# Brakelight_v3.net
KiCad netlist of a schematic drawn in EAGLE
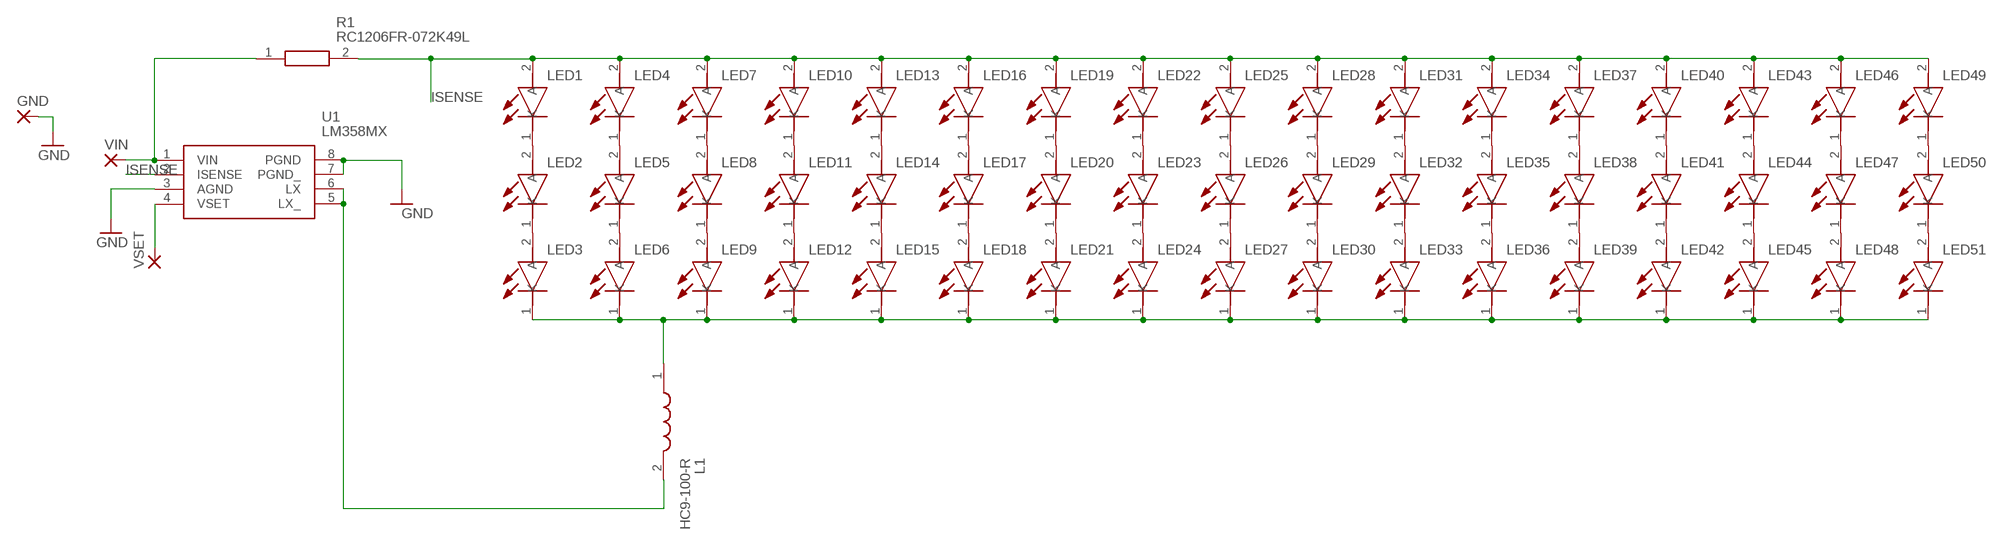
[diagram p0: schematic, sheet 1]

(export (version "E")
  (design (tool "Eeschema 10.0.6"))
  (components
    (comp (ref "GND")
      (value "2,54/1,1")
      (footprint "eagle-import:2,54_1,1")
      (libsource (lib "eagle-import") (part "2,54/1,1"))
    )
    (comp (ref "L1")
      (value "HC9-100-R")
      (footprint "eagle-import:INDPM141131X770N")
      (fields (field (name "MOUSER_PART_NUMBER") "704-HC9-100-R"))
      (libsource (lib "eagle-import") (part "HC9-100-R"))
    )
    (comp (ref "LED1")
      (value "SSL-LX5093TC")
      (footprint "eagle-import:SSL-LX5093SGC_B")
      (fields (field (name "MOUSER_PART_NUMBER") "696-SSL-LX5093TC"))
      (libsource (lib "eagle-import") (part "SSL-LX5093TC"))
    )
    (comp (ref "LED2")
      (value "SSL-LX5093TC")
      (footprint "eagle-import:SSL-LX5093SGC_B")
      (fields (field (name "MOUSER_PART_NUMBER") "696-SSL-LX5093TC"))
      (libsource (lib "eagle-import") (part "SSL-LX5093TC"))
    )
    (comp (ref "LED3")
      (value "SSL-LX5093TC")
      (footprint "eagle-import:SSL-LX5093SGC_B")
      (fields (field (name "MOUSER_PART_NUMBER") "696-SSL-LX5093TC"))
      (libsource (lib "eagle-import") (part "SSL-LX5093TC"))
    )
    (comp (ref "LED4")
      (value "SSL-LX5093TC")
      (footprint "eagle-import:SSL-LX5093SGC_B")
      (fields (field (name "MOUSER_PART_NUMBER") "696-SSL-LX5093TC"))
      (libsource (lib "eagle-import") (part "SSL-LX5093TC"))
    )
    (comp (ref "LED5")
      (value "SSL-LX5093TC")
      (footprint "eagle-import:SSL-LX5093SGC_B")
      (fields (field (name "MOUSER_PART_NUMBER") "696-SSL-LX5093TC"))
      (libsource (lib "eagle-import") (part "SSL-LX5093TC"))
    )
    (comp (ref "LED6")
      (value "SSL-LX5093TC")
      (footprint "eagle-import:SSL-LX5093SGC_B")
      (fields (field (name "MOUSER_PART_NUMBER") "696-SSL-LX5093TC"))
      (libsource (lib "eagle-import") (part "SSL-LX5093TC"))
    )
    (comp (ref "LED7")
      (value "SSL-LX5093TC")
      (footprint "eagle-import:SSL-LX5093SGC_B")
      (fields (field (name "MOUSER_PART_NUMBER") "696-SSL-LX5093TC"))
      (libsource (lib "eagle-import") (part "SSL-LX5093TC"))
    )
    (comp (ref "LED8")
      (value "SSL-LX5093TC")
      (footprint "eagle-import:SSL-LX5093SGC_B")
      (fields (field (name "MOUSER_PART_NUMBER") "696-SSL-LX5093TC"))
      (libsource (lib "eagle-import") (part "SSL-LX5093TC"))
    )
    (comp (ref "LED9")
      (value "SSL-LX5093TC")
      (footprint "eagle-import:SSL-LX5093SGC_B")
      (fields (field (name "MOUSER_PART_NUMBER") "696-SSL-LX5093TC"))
      (libsource (lib "eagle-import") (part "SSL-LX5093TC"))
    )
    (comp (ref "LED10")
      (value "SSL-LX5093TC")
      (footprint "eagle-import:SSL-LX5093SGC_B")
      (fields (field (name "MOUSER_PART_NUMBER") "696-SSL-LX5093TC"))
      (libsource (lib "eagle-import") (part "SSL-LX5093TC"))
    )
    (comp (ref "LED11")
      (value "SSL-LX5093TC")
      (footprint "eagle-import:SSL-LX5093SGC_B")
      (fields (field (name "MOUSER_PART_NUMBER") "696-SSL-LX5093TC"))
      (libsource (lib "eagle-import") (part "SSL-LX5093TC"))
    )
    (comp (ref "LED12")
      (value "SSL-LX5093TC")
      (footprint "eagle-import:SSL-LX5093SGC_B")
      (fields (field (name "MOUSER_PART_NUMBER") "696-SSL-LX5093TC"))
      (libsource (lib "eagle-import") (part "SSL-LX5093TC"))
    )
    (comp (ref "LED13")
      (value "SSL-LX5093TC")
      (footprint "eagle-import:SSL-LX5093SGC_B")
      (fields (field (name "MOUSER_PART_NUMBER") "696-SSL-LX5093TC"))
      (libsource (lib "eagle-import") (part "SSL-LX5093TC"))
    )
    (comp (ref "LED14")
      (value "SSL-LX5093TC")
      (footprint "eagle-import:SSL-LX5093SGC_B")
      (fields (field (name "MOUSER_PART_NUMBER") "696-SSL-LX5093TC"))
      (libsource (lib "eagle-import") (part "SSL-LX5093TC"))
    )
    (comp (ref "LED15")
      (value "SSL-LX5093TC")
      (footprint "eagle-import:SSL-LX5093SGC_B")
      (fields (field (name "MOUSER_PART_NUMBER") "696-SSL-LX5093TC"))
      (libsource (lib "eagle-import") (part "SSL-LX5093TC"))
    )
    (comp (ref "LED16")
      (value "SSL-LX5093TC")
      (footprint "eagle-import:SSL-LX5093SGC_B")
      (fields (field (name "MOUSER_PART_NUMBER") "696-SSL-LX5093TC"))
      (libsource (lib "eagle-import") (part "SSL-LX5093TC"))
    )
    (comp (ref "LED17")
      (value "SSL-LX5093TC")
      (footprint "eagle-import:SSL-LX5093SGC_B")
      (fields (field (name "MOUSER_PART_NUMBER") "696-SSL-LX5093TC"))
      (libsource (lib "eagle-import") (part "SSL-LX5093TC"))
    )
    (comp (ref "LED18")
      (value "SSL-LX5093TC")
      (footprint "eagle-import:SSL-LX5093SGC_B")
      (fields (field (name "MOUSER_PART_NUMBER") "696-SSL-LX5093TC"))
      (libsource (lib "eagle-import") (part "SSL-LX5093TC"))
    )
    (comp (ref "LED19")
      (value "SSL-LX5093TC")
      (footprint "eagle-import:SSL-LX5093SGC_B")
      (fields (field (name "MOUSER_PART_NUMBER") "696-SSL-LX5093TC"))
      (libsource (lib "eagle-import") (part "SSL-LX5093TC"))
    )
    (comp (ref "LED20")
      (value "SSL-LX5093TC")
      (footprint "eagle-import:SSL-LX5093SGC_B")
      (fields (field (name "MOUSER_PART_NUMBER") "696-SSL-LX5093TC"))
      (libsource (lib "eagle-import") (part "SSL-LX5093TC"))
    )
    (comp (ref "LED21")
      (value "SSL-LX5093TC")
      (footprint "eagle-import:SSL-LX5093SGC_B")
      (fields (field (name "MOUSER_PART_NUMBER") "696-SSL-LX5093TC"))
      (libsource (lib "eagle-import") (part "SSL-LX5093TC"))
    )
    (comp (ref "LED22")
      (value "SSL-LX5093TC")
      (footprint "eagle-import:SSL-LX5093SGC_B")
      (fields (field (name "MOUSER_PART_NUMBER") "696-SSL-LX5093TC"))
      (libsource (lib "eagle-import") (part "SSL-LX5093TC"))
    )
    (comp (ref "LED23")
      (value "SSL-LX5093TC")
      (footprint "eagle-import:SSL-LX5093SGC_B")
      (fields (field (name "MOUSER_PART_NUMBER") "696-SSL-LX5093TC"))
      (libsource (lib "eagle-import") (part "SSL-LX5093TC"))
    )
    (comp (ref "LED24")
      (value "SSL-LX5093TC")
      (footprint "eagle-import:SSL-LX5093SGC_B")
      (fields (field (name "MOUSER_PART_NUMBER") "696-SSL-LX5093TC"))
      (libsource (lib "eagle-import") (part "SSL-LX5093TC"))
    )
    (comp (ref "LED25")
      (value "SSL-LX5093TC")
      (footprint "eagle-import:SSL-LX5093SGC_B")
      (fields (field (name "MOUSER_PART_NUMBER") "696-SSL-LX5093TC"))
      (libsource (lib "eagle-import") (part "SSL-LX5093TC"))
    )
    (comp (ref "LED26")
      (value "SSL-LX5093TC")
      (footprint "eagle-import:SSL-LX5093SGC_B")
      (fields (field (name "MOUSER_PART_NUMBER") "696-SSL-LX5093TC"))
      (libsource (lib "eagle-import") (part "SSL-LX5093TC"))
    )
    (comp (ref "LED27")
      (value "SSL-LX5093TC")
      (footprint "eagle-import:SSL-LX5093SGC_B")
      (fields (field (name "MOUSER_PART_NUMBER") "696-SSL-LX5093TC"))
      (libsource (lib "eagle-import") (part "SSL-LX5093TC"))
    )
    (comp (ref "LED28")
      (value "SSL-LX5093TC")
      (footprint "eagle-import:SSL-LX5093SGC_B")
      (fields (field (name "MOUSER_PART_NUMBER") "696-SSL-LX5093TC"))
      (libsource (lib "eagle-import") (part "SSL-LX5093TC"))
    )
    (comp (ref "LED29")
      (value "SSL-LX5093TC")
      (footprint "eagle-import:SSL-LX5093SGC_B")
      (fields (field (name "MOUSER_PART_NUMBER") "696-SSL-LX5093TC"))
      (libsource (lib "eagle-import") (part "SSL-LX5093TC"))
    )
    (comp (ref "LED30")
      (value "SSL-LX5093TC")
      (footprint "eagle-import:SSL-LX5093SGC_B")
      (fields (field (name "MOUSER_PART_NUMBER") "696-SSL-LX5093TC"))
      (libsource (lib "eagle-import") (part "SSL-LX5093TC"))
    )
    (comp (ref "LED31")
      (value "SSL-LX5093TC")
      (footprint "eagle-import:SSL-LX5093SGC_B")
      (fields (field (name "MOUSER_PART_NUMBER") "696-SSL-LX5093TC"))
      (libsource (lib "eagle-import") (part "SSL-LX5093TC"))
    )
    (comp (ref "LED32")
      (value "SSL-LX5093TC")
      (footprint "eagle-import:SSL-LX5093SGC_B")
      (fields (field (name "MOUSER_PART_NUMBER") "696-SSL-LX5093TC"))
      (libsource (lib "eagle-import") (part "SSL-LX5093TC"))
    )
    (comp (ref "LED33")
      (value "SSL-LX5093TC")
      (footprint "eagle-import:SSL-LX5093SGC_B")
      (fields (field (name "MOUSER_PART_NUMBER") "696-SSL-LX5093TC"))
      (libsource (lib "eagle-import") (part "SSL-LX5093TC"))
    )
    (comp (ref "LED34")
      (value "SSL-LX5093TC")
      (footprint "eagle-import:SSL-LX5093SGC_B")
      (fields (field (name "MOUSER_PART_NUMBER") "696-SSL-LX5093TC"))
      (libsource (lib "eagle-import") (part "SSL-LX5093TC"))
    )
    (comp (ref "LED35")
      (value "SSL-LX5093TC")
      (footprint "eagle-import:SSL-LX5093SGC_B")
      (fields (field (name "MOUSER_PART_NUMBER") "696-SSL-LX5093TC"))
      (libsource (lib "eagle-import") (part "SSL-LX5093TC"))
    )
    (comp (ref "LED36")
      (value "SSL-LX5093TC")
      (footprint "eagle-import:SSL-LX5093SGC_B")
      (fields (field (name "MOUSER_PART_NUMBER") "696-SSL-LX5093TC"))
      (libsource (lib "eagle-import") (part "SSL-LX5093TC"))
    )
    (comp (ref "LED37")
      (value "SSL-LX5093TC")
      (footprint "eagle-import:SSL-LX5093SGC_B")
      (fields (field (name "MOUSER_PART_NUMBER") "696-SSL-LX5093TC"))
      (libsource (lib "eagle-import") (part "SSL-LX5093TC"))
    )
    (comp (ref "LED38")
      (value "SSL-LX5093TC")
      (footprint "eagle-import:SSL-LX5093SGC_B")
      (fields (field (name "MOUSER_PART_NUMBER") "696-SSL-LX5093TC"))
      (libsource (lib "eagle-import") (part "SSL-LX5093TC"))
    )
    (comp (ref "LED39")
      (value "SSL-LX5093TC")
      (footprint "eagle-import:SSL-LX5093SGC_B")
      (fields (field (name "MOUSER_PART_NUMBER") "696-SSL-LX5093TC"))
      (libsource (lib "eagle-import") (part "SSL-LX5093TC"))
    )
    (comp (ref "LED40")
      (value "SSL-LX5093TC")
      (footprint "eagle-import:SSL-LX5093SGC_B")
      (fields (field (name "MOUSER_PART_NUMBER") "696-SSL-LX5093TC"))
      (libsource (lib "eagle-import") (part "SSL-LX5093TC"))
    )
    (comp (ref "LED41")
      (value "SSL-LX5093TC")
      (footprint "eagle-import:SSL-LX5093SGC_B")
      (fields (field (name "MOUSER_PART_NUMBER") "696-SSL-LX5093TC"))
      (libsource (lib "eagle-import") (part "SSL-LX5093TC"))
    )
    (comp (ref "LED42")
      (value "SSL-LX5093TC")
      (footprint "eagle-import:SSL-LX5093SGC_B")
      (fields (field (name "MOUSER_PART_NUMBER") "696-SSL-LX5093TC"))
      (libsource (lib "eagle-import") (part "SSL-LX5093TC"))
    )
    (comp (ref "LED43")
      (value "SSL-LX5093TC")
      (footprint "eagle-import:SSL-LX5093SGC_B")
      (fields (field (name "MOUSER_PART_NUMBER") "696-SSL-LX5093TC"))
      (libsource (lib "eagle-import") (part "SSL-LX5093TC"))
    )
    (comp (ref "LED44")
      (value "SSL-LX5093TC")
      (footprint "eagle-import:SSL-LX5093SGC_B")
      (fields (field (name "MOUSER_PART_NUMBER") "696-SSL-LX5093TC"))
      (libsource (lib "eagle-import") (part "SSL-LX5093TC"))
    )
    (comp (ref "LED45")
      (value "SSL-LX5093TC")
      (footprint "eagle-import:SSL-LX5093SGC_B")
      (fields (field (name "MOUSER_PART_NUMBER") "696-SSL-LX5093TC"))
      (libsource (lib "eagle-import") (part "SSL-LX5093TC"))
    )
    (comp (ref "LED46")
      (value "SSL-LX5093TC")
      (footprint "eagle-import:SSL-LX5093SGC_B")
      (fields (field (name "MOUSER_PART_NUMBER") "696-SSL-LX5093TC"))
      (libsource (lib "eagle-import") (part "SSL-LX5093TC"))
    )
    (comp (ref "LED47")
      (value "SSL-LX5093TC")
      (footprint "eagle-import:SSL-LX5093SGC_B")
      (fields (field (name "MOUSER_PART_NUMBER") "696-SSL-LX5093TC"))
      (libsource (lib "eagle-import") (part "SSL-LX5093TC"))
    )
    (comp (ref "LED48")
      (value "SSL-LX5093TC")
      (footprint "eagle-import:SSL-LX5093SGC_B")
      (fields (field (name "MOUSER_PART_NUMBER") "696-SSL-LX5093TC"))
      (libsource (lib "eagle-import") (part "SSL-LX5093TC"))
    )
    (comp (ref "LED49")
      (value "SSL-LX5093TC")
      (footprint "eagle-import:SSL-LX5093SGC_B")
      (fields (field (name "MOUSER_PART_NUMBER") "696-SSL-LX5093TC"))
      (libsource (lib "eagle-import") (part "SSL-LX5093TC"))
    )
    (comp (ref "LED50")
      (value "SSL-LX5093TC")
      (footprint "eagle-import:SSL-LX5093SGC_B")
      (fields (field (name "MOUSER_PART_NUMBER") "696-SSL-LX5093TC"))
      (libsource (lib "eagle-import") (part "SSL-LX5093TC"))
    )
    (comp (ref "LED51")
      (value "SSL-LX5093TC")
      (footprint "eagle-import:SSL-LX5093SGC_B")
      (fields (field (name "MOUSER_PART_NUMBER") "696-SSL-LX5093TC"))
      (libsource (lib "eagle-import") (part "SSL-LX5093TC"))
    )
    (comp (ref "R1")
      (value "RC1206FR-072K49L")
      (footprint "eagle-import:RESC3116X65N")
      (fields (field (name "MOUSER_PART_NUMBER") "603-RC1206FR-072K49L"))
      (libsource (lib "eagle-import") (part "RC1206FR-072K49L"))
    )
    (comp (ref "U1")
      (value "LM358MX")
      (footprint "eagle-import:SOP127P600X180-8N")
      (fields (field (name "MOUSER_PART_NUMBER") "512-LM358MX"))
      (libsource (lib "eagle-import") (part "LM358MX"))
    )
    (comp (ref "VIN")
      (value "2,54/1,1")
      (footprint "eagle-import:2,54_1,1")
      (libsource (lib "eagle-import") (part "2,54/1,1"))
    )
    (comp (ref "VSET")
      (value "2,54/1,1")
      (footprint "eagle-import:2,54_1,1")
      (libsource (lib "eagle-import") (part "2,54/1,1"))
    )
  )
  (nets
    (net (code "1") (name "/ISENSE") (class "Default")
      (node (ref "LED1") (pin "2") (pinfunction "A_2") (pintype "bidirectional"))
      (node (ref "LED10") (pin "2") (pinfunction "A_2") (pintype "bidirectional"))
      (node (ref "LED13") (pin "2") (pinfunction "A_2") (pintype "bidirectional"))
      (node (ref "LED16") (pin "2") (pinfunction "A_2") (pintype "bidirectional"))
      (node (ref "LED19") (pin "2") (pinfunction "A_2") (pintype "bidirectional"))
      (node (ref "LED22") (pin "2") (pinfunction "A_2") (pintype "bidirectional"))
      (node (ref "LED25") (pin "2") (pinfunction "A_2") (pintype "bidirectional"))
      (node (ref "LED28") (pin "2") (pinfunction "A_2") (pintype "bidirectional"))
      (node (ref "LED31") (pin "2") (pinfunction "A_2") (pintype "bidirectional"))
      (node (ref "LED34") (pin "2") (pinfunction "A_2") (pintype "bidirectional"))
      (node (ref "LED37") (pin "2") (pinfunction "A_2") (pintype "bidirectional"))
      (node (ref "LED4") (pin "2") (pinfunction "A_2") (pintype "bidirectional"))
      (node (ref "LED40") (pin "2") (pinfunction "A_2") (pintype "bidirectional"))
      (node (ref "LED43") (pin "2") (pinfunction "A_2") (pintype "bidirectional"))
      (node (ref "LED46") (pin "2") (pinfunction "A_2") (pintype "bidirectional"))
      (node (ref "LED49") (pin "2") (pinfunction "A_2") (pintype "bidirectional"))
      (node (ref "LED7") (pin "2") (pinfunction "A_2") (pintype "bidirectional"))
      (node (ref "R1") (pin "2") (pinfunction "2_2") (pintype "bidirectional"))
      (node (ref "U1") (pin "2") (pinfunction "ISENSE_2") (pintype "bidirectional"))
    )
    (net (code "2") (name "GND") (class "Default")
      (node (ref "GND") (pin "1") (pinfunction "P_1") (pintype "passive"))
      (node (ref "U1") (pin "3") (pinfunction "AGND_3") (pintype "bidirectional"))
      (node (ref "U1") (pin "7") (pinfunction "PGND__7") (pintype "bidirectional"))
      (node (ref "U1") (pin "8") (pinfunction "PGND_8") (pintype "bidirectional"))
    )
    (net (code "3") (name "Net-(LED1-K)") (class "Default")
      (node (ref "LED1") (pin "1") (pinfunction "K_1") (pintype "bidirectional"))
      (node (ref "LED2") (pin "2") (pinfunction "A_2") (pintype "bidirectional"))
    )
    (net (code "4") (name "Net-(LED2-K)") (class "Default")
      (node (ref "LED2") (pin "1") (pinfunction "K_1") (pintype "bidirectional"))
      (node (ref "LED3") (pin "2") (pinfunction "A_2") (pintype "bidirectional"))
    )
    (net (code "5") (name "Net-(LED4-K)") (class "Default")
      (node (ref "LED4") (pin "1") (pinfunction "K_1") (pintype "bidirectional"))
      (node (ref "LED5") (pin "2") (pinfunction "A_2") (pintype "bidirectional"))
    )
    (net (code "6") (name "Net-(LED5-K)") (class "Default")
      (node (ref "LED5") (pin "1") (pinfunction "K_1") (pintype "bidirectional"))
      (node (ref "LED6") (pin "2") (pinfunction "A_2") (pintype "bidirectional"))
    )
    (net (code "7") (name "Net-(LED7-K)") (class "Default")
      (node (ref "LED7") (pin "1") (pinfunction "K_1") (pintype "bidirectional"))
      (node (ref "LED8") (pin "2") (pinfunction "A_2") (pintype "bidirectional"))
    )
    (net (code "8") (name "Net-(LED8-K)") (class "Default")
      (node (ref "LED8") (pin "1") (pinfunction "K_1") (pintype "bidirectional"))
      (node (ref "LED9") (pin "2") (pinfunction "A_2") (pintype "bidirectional"))
    )
    (net (code "9") (name "Net-(LED10-K)") (class "Default")
      (node (ref "LED10") (pin "1") (pinfunction "K_1") (pintype "bidirectional"))
      (node (ref "LED11") (pin "2") (pinfunction "A_2") (pintype "bidirectional"))
    )
    (net (code "10") (name "Net-(LED11-K)") (class "Default")
      (node (ref "LED11") (pin "1") (pinfunction "K_1") (pintype "bidirectional"))
      (node (ref "LED12") (pin "2") (pinfunction "A_2") (pintype "bidirectional"))
    )
    (net (code "11") (name "Net-(LED12-K)") (class "Default")
      (node (ref "L1") (pin "1") (pinfunction "1_1") (pintype "bidirectional"))
      (node (ref "LED12") (pin "1") (pinfunction "K_1") (pintype "bidirectional"))
      (node (ref "LED15") (pin "1") (pinfunction "K_1") (pintype "bidirectional"))
      (node (ref "LED18") (pin "1") (pinfunction "K_1") (pintype "bidirectional"))
      (node (ref "LED21") (pin "1") (pinfunction "K_1") (pintype "bidirectional"))
      (node (ref "LED24") (pin "1") (pinfunction "K_1") (pintype "bidirectional"))
      (node (ref "LED27") (pin "1") (pinfunction "K_1") (pintype "bidirectional"))
      (node (ref "LED3") (pin "1") (pinfunction "K_1") (pintype "bidirectional"))
      (node (ref "LED30") (pin "1") (pinfunction "K_1") (pintype "bidirectional"))
      (node (ref "LED33") (pin "1") (pinfunction "K_1") (pintype "bidirectional"))
      (node (ref "LED36") (pin "1") (pinfunction "K_1") (pintype "bidirectional"))
      (node (ref "LED39") (pin "1") (pinfunction "K_1") (pintype "bidirectional"))
      (node (ref "LED42") (pin "1") (pinfunction "K_1") (pintype "bidirectional"))
      (node (ref "LED45") (pin "1") (pinfunction "K_1") (pintype "bidirectional"))
      (node (ref "LED48") (pin "1") (pinfunction "K_1") (pintype "bidirectional"))
      (node (ref "LED51") (pin "1") (pinfunction "K_1") (pintype "bidirectional"))
      (node (ref "LED6") (pin "1") (pinfunction "K_1") (pintype "bidirectional"))
      (node (ref "LED9") (pin "1") (pinfunction "K_1") (pintype "bidirectional"))
    )
    (net (code "12") (name "Net-(LED13-K)") (class "Default")
      (node (ref "LED13") (pin "1") (pinfunction "K_1") (pintype "bidirectional"))
      (node (ref "LED14") (pin "2") (pinfunction "A_2") (pintype "bidirectional"))
    )
    (net (code "13") (name "Net-(LED14-K)") (class "Default")
      (node (ref "LED14") (pin "1") (pinfunction "K_1") (pintype "bidirectional"))
      (node (ref "LED15") (pin "2") (pinfunction "A_2") (pintype "bidirectional"))
    )
    (net (code "14") (name "Net-(LED16-K)") (class "Default")
      (node (ref "LED16") (pin "1") (pinfunction "K_1") (pintype "bidirectional"))
      (node (ref "LED17") (pin "2") (pinfunction "A_2") (pintype "bidirectional"))
    )
    (net (code "15") (name "Net-(LED17-K)") (class "Default")
      (node (ref "LED17") (pin "1") (pinfunction "K_1") (pintype "bidirectional"))
      (node (ref "LED18") (pin "2") (pinfunction "A_2") (pintype "bidirectional"))
    )
    (net (code "16") (name "Net-(LED19-K)") (class "Default")
      (node (ref "LED19") (pin "1") (pinfunction "K_1") (pintype "bidirectional"))
      (node (ref "LED20") (pin "2") (pinfunction "A_2") (pintype "bidirectional"))
    )
    (net (code "17") (name "Net-(LED20-K)") (class "Default")
      (node (ref "LED20") (pin "1") (pinfunction "K_1") (pintype "bidirectional"))
      (node (ref "LED21") (pin "2") (pinfunction "A_2") (pintype "bidirectional"))
    )
    (net (code "18") (name "Net-(LED22-K)") (class "Default")
      (node (ref "LED22") (pin "1") (pinfunction "K_1") (pintype "bidirectional"))
      (node (ref "LED23") (pin "2") (pinfunction "A_2") (pintype "bidirectional"))
    )
    (net (code "19") (name "Net-(LED23-K)") (class "Default")
      (node (ref "LED23") (pin "1") (pinfunction "K_1") (pintype "bidirectional"))
      (node (ref "LED24") (pin "2") (pinfunction "A_2") (pintype "bidirectional"))
    )
    (net (code "20") (name "Net-(LED25-K)") (class "Default")
      (node (ref "LED25") (pin "1") (pinfunction "K_1") (pintype "bidirectional"))
      (node (ref "LED26") (pin "2") (pinfunction "A_2") (pintype "bidirectional"))
    )
    (net (code "21") (name "Net-(LED26-K)") (class "Default")
      (node (ref "LED26") (pin "1") (pinfunction "K_1") (pintype "bidirectional"))
      (node (ref "LED27") (pin "2") (pinfunction "A_2") (pintype "bidirectional"))
    )
    (net (code "22") (name "Net-(LED28-K)") (class "Default")
      (node (ref "LED28") (pin "1") (pinfunction "K_1") (pintype "bidirectional"))
      (node (ref "LED29") (pin "2") (pinfunction "A_2") (pintype "bidirectional"))
    )
    (net (code "23") (name "Net-(LED29-K)") (class "Default")
      (node (ref "LED29") (pin "1") (pinfunction "K_1") (pintype "bidirectional"))
      (node (ref "LED30") (pin "2") (pinfunction "A_2") (pintype "bidirectional"))
    )
    (net (code "24") (name "Net-(LED31-K)") (class "Default")
      (node (ref "LED31") (pin "1") (pinfunction "K_1") (pintype "bidirectional"))
      (node (ref "LED32") (pin "2") (pinfunction "A_2") (pintype "bidirectional"))
    )
    (net (code "25") (name "Net-(LED32-K)") (class "Default")
      (node (ref "LED32") (pin "1") (pinfunction "K_1") (pintype "bidirectional"))
      (node (ref "LED33") (pin "2") (pinfunction "A_2") (pintype "bidirectional"))
    )
    (net (code "26") (name "Net-(LED34-K)") (class "Default")
      (node (ref "LED34") (pin "1") (pinfunction "K_1") (pintype "bidirectional"))
      (node (ref "LED35") (pin "2") (pinfunction "A_2") (pintype "bidirectional"))
    )
    (net (code "27") (name "Net-(LED35-K)") (class "Default")
      (node (ref "LED35") (pin "1") (pinfunction "K_1") (pintype "bidirectional"))
      (node (ref "LED36") (pin "2") (pinfunction "A_2") (pintype "bidirectional"))
    )
    (net (code "28") (name "Net-(LED37-K)") (class "Default")
      (node (ref "LED37") (pin "1") (pinfunction "K_1") (pintype "bidirectional"))
      (node (ref "LED38") (pin "2") (pinfunction "A_2") (pintype "bidirectional"))
    )
    (net (code "29") (name "Net-(LED38-K)") (class "Default")
      (node (ref "LED38") (pin "1") (pinfunction "K_1") (pintype "bidirectional"))
      (node (ref "LED39") (pin "2") (pinfunction "A_2") (pintype "bidirectional"))
    )
    (net (code "30") (name "Net-(LED40-K)") (class "Default")
      (node (ref "LED40") (pin "1") (pinfunction "K_1") (pintype "bidirectional"))
      (node (ref "LED41") (pin "2") (pinfunction "A_2") (pintype "bidirectional"))
    )
    (net (code "31") (name "Net-(LED41-K)") (class "Default")
      (node (ref "LED41") (pin "1") (pinfunction "K_1") (pintype "bidirectional"))
      (node (ref "LED42") (pin "2") (pinfunction "A_2") (pintype "bidirectional"))
    )
    (net (code "32") (name "Net-(LED43-K)") (class "Default")
      (node (ref "LED43") (pin "1") (pinfunction "K_1") (pintype "bidirectional"))
      (node (ref "LED44") (pin "2") (pinfunction "A_2") (pintype "bidirectional"))
    )
    (net (code "33") (name "Net-(LED44-K)") (class "Default")
      (node (ref "LED44") (pin "1") (pinfunction "K_1") (pintype "bidirectional"))
      (node (ref "LED45") (pin "2") (pinfunction "A_2") (pintype "bidirectional"))
    )
    (net (code "34") (name "Net-(LED46-K)") (class "Default")
      (node (ref "LED46") (pin "1") (pinfunction "K_1") (pintype "bidirectional"))
      (node (ref "LED47") (pin "2") (pinfunction "A_2") (pintype "bidirectional"))
    )
    (net (code "35") (name "Net-(LED47-K)") (class "Default")
      (node (ref "LED47") (pin "1") (pinfunction "K_1") (pintype "bidirectional"))
      (node (ref "LED48") (pin "2") (pinfunction "A_2") (pintype "bidirectional"))
    )
    (net (code "36") (name "Net-(LED49-K)") (class "Default")
      (node (ref "LED49") (pin "1") (pinfunction "K_1") (pintype "bidirectional"))
      (node (ref "LED50") (pin "2") (pinfunction "A_2") (pintype "bidirectional"))
    )
    (net (code "37") (name "Net-(LED50-K)") (class "Default")
      (node (ref "LED50") (pin "1") (pinfunction "K_1") (pintype "bidirectional"))
      (node (ref "LED51") (pin "2") (pinfunction "A_2") (pintype "bidirectional"))
    )
    (net (code "38") (name "Net-(U1-LX)") (class "Default")
      (node (ref "L1") (pin "2") (pinfunction "2_2") (pintype "bidirectional"))
      (node (ref "U1") (pin "5") (pinfunction "LX__5") (pintype "bidirectional"))
      (node (ref "U1") (pin "6") (pinfunction "LX_6") (pintype "bidirectional"))
    )
    (net (code "39") (name "Net-(U1-VIN)") (class "Default")
      (node (ref "R1") (pin "1") (pinfunction "1_1") (pintype "bidirectional"))
      (node (ref "U1") (pin "1") (pinfunction "VIN_1") (pintype "bidirectional"))
      (node (ref "VIN") (pin "1") (pinfunction "P_1") (pintype "passive"))
    )
    (net (code "40") (name "Net-(U1-VSET)") (class "Default")
      (node (ref "U1") (pin "4") (pinfunction "VSET_4") (pintype "bidirectional"))
      (node (ref "VSET") (pin "1") (pinfunction "P_1") (pintype "passive"))
    )
  )
)
